# 400_POWER_STAGE.net
KiCad netlist of a schematic drawn in Altium Designer
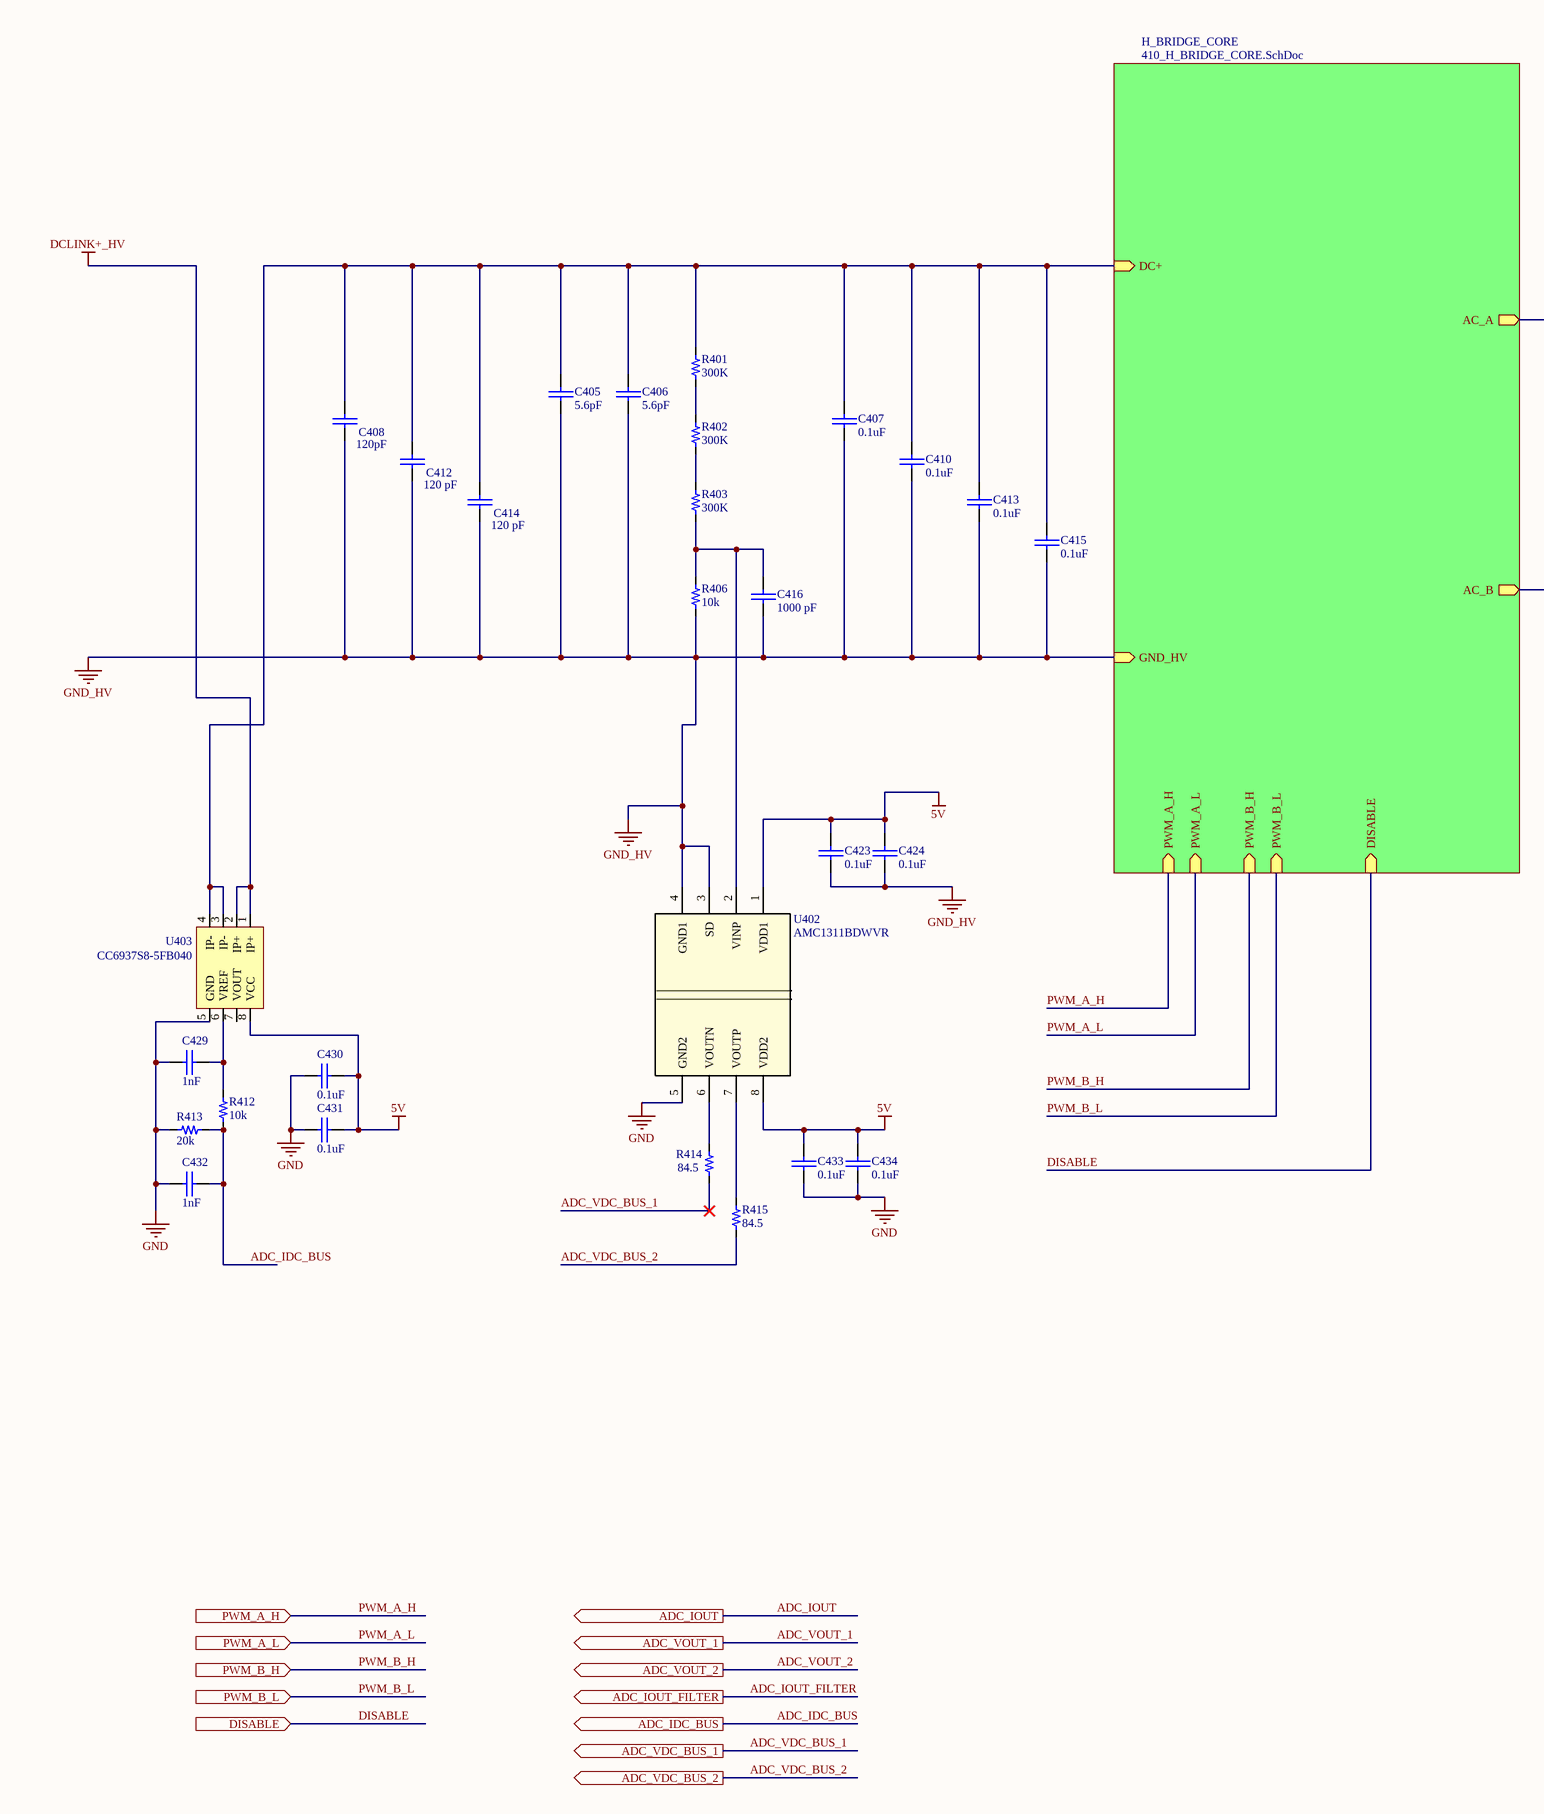
[diagram p0: 400_POWER_STAGE.SchDoc, left]
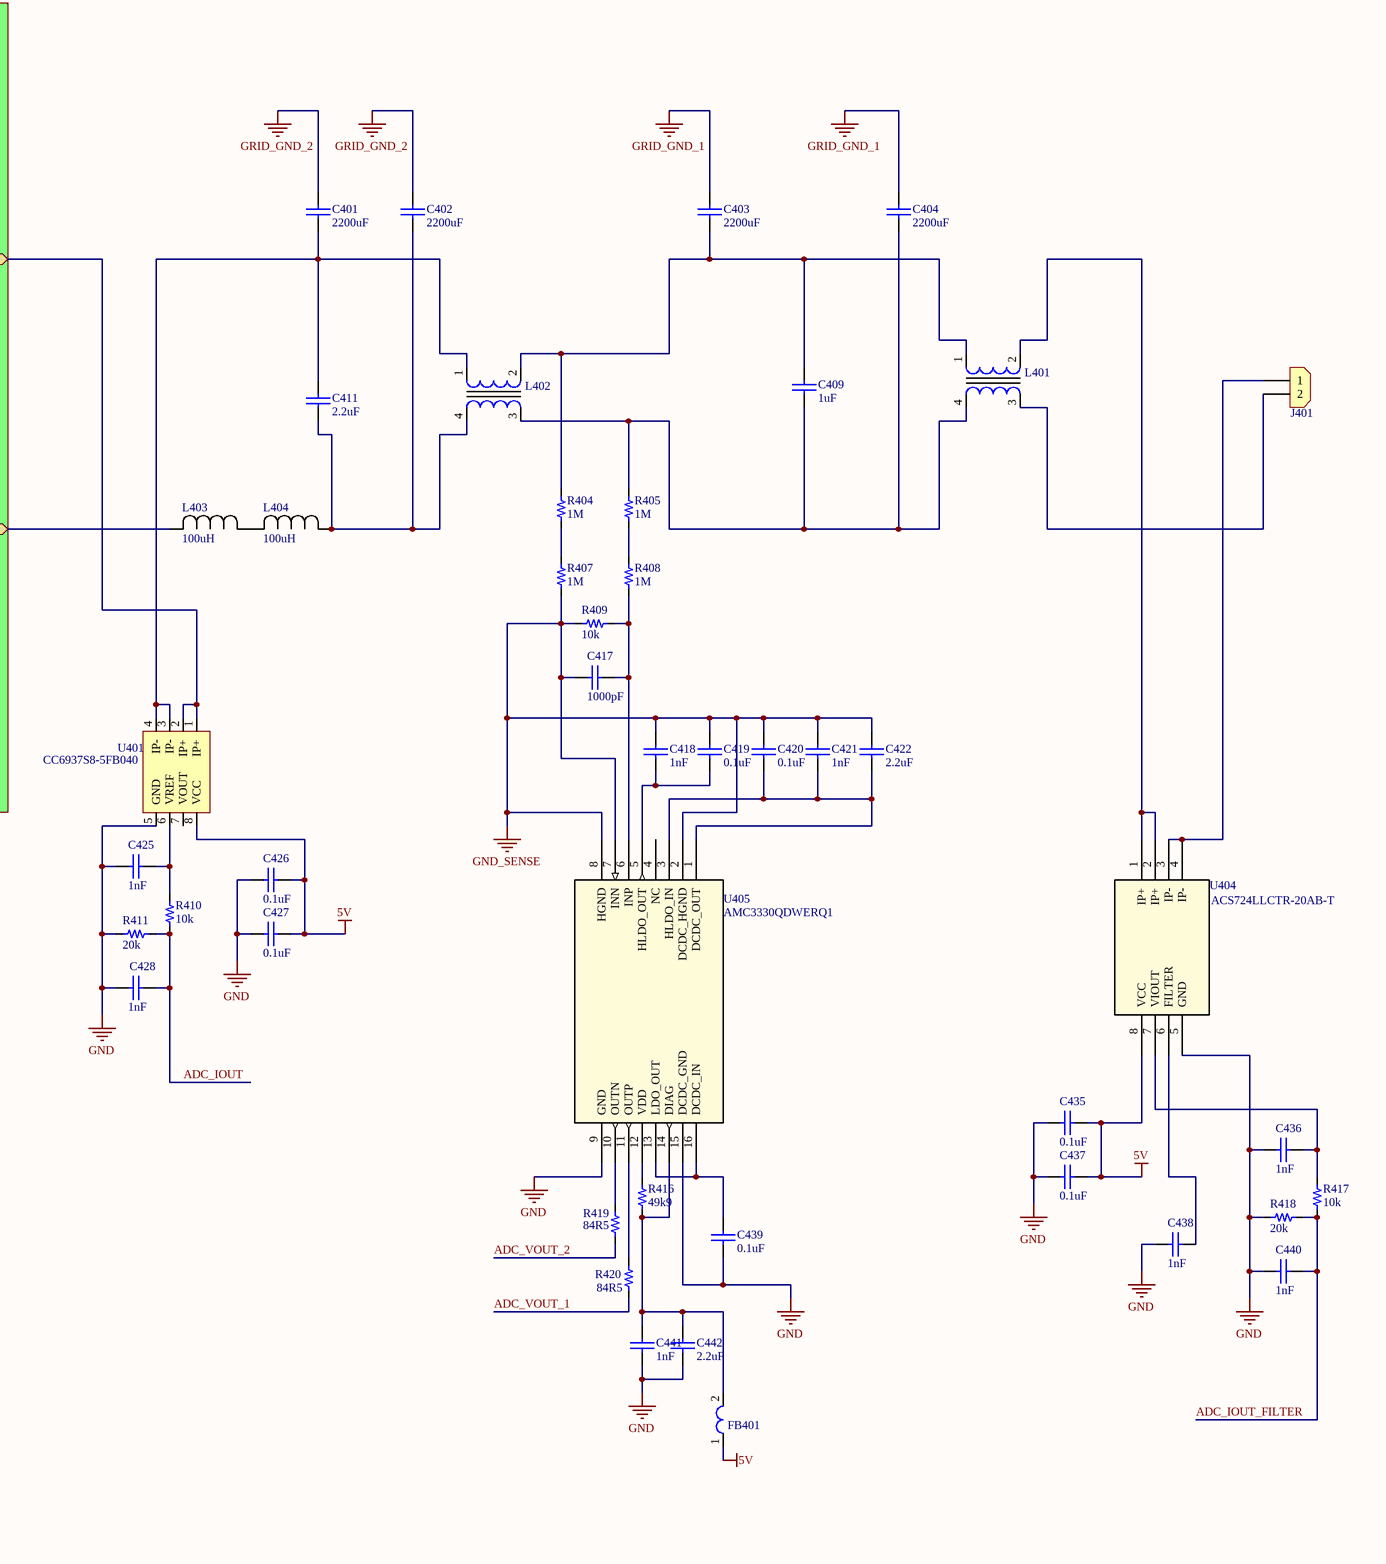
[diagram p1: 400_POWER_STAGE.SchDoc, right]

(export (version "E")
  (design (tool "Eeschema 10.0.6"))
  (components
    (comp (ref "C401")
      (value "2200uF")
      (footprint "Through Hole,P=7.5mm")
      (description "2200 pF ±20% 300VAC Ceramic Capacitor E Radial, Disc")
      (fields
        (field (name "MANUFACTURER") "Murata Electronics")
        (field (name "MANUFACTURER PART NUMBER") "DE6E3KJ222MN3A")
      )
      (libsource (lib "shared_lib_1") (part "CAP_CER_2200PF_300VAC"))
    )
    (comp (ref "C402")
      (value "2200uF")
      (footprint "Through Hole,P=7.5mm")
      (description "2200 pF ±20% 300VAC Ceramic Capacitor E Radial, Disc")
      (fields
        (field (name "MANUFACTURER") "Murata Electronics")
        (field (name "MANUFACTURER PART NUMBER") "DE6E3KJ222MN3A")
      )
      (libsource (lib "shared_lib_1") (part "CAP_CER_2200PF_300VAC"))
    )
    (comp (ref "C403")
      (value "2200uF")
      (footprint "Through Hole,P=7.5mm")
      (description "2200 pF ±20% 300VAC Ceramic Capacitor E Radial, Disc")
      (fields
        (field (name "MANUFACTURER") "Murata Electronics")
        (field (name "MANUFACTURER PART NUMBER") "DE6E3KJ222MN3A")
      )
      (libsource (lib "shared_lib_1") (part "CAP_CER_2200PF_300VAC"))
    )
    (comp (ref "C404")
      (value "2200uF")
      (footprint "Through Hole,P=7.5mm")
      (description "2200 pF ±20% 300VAC Ceramic Capacitor E Radial, Disc")
      (fields
        (field (name "MANUFACTURER") "Murata Electronics")
        (field (name "MANUFACTURER PART NUMBER") "DE6E3KJ222MN3A")
      )
      (libsource (lib "shared_lib_1") (part "CAP_CER_2200PF_300VAC"))
    )
    (comp (ref "C405")
      (value "5.6pF")
      (footprint "0603_cap")
      (description "5.6pF C0G 250V 0603 Ceramic Capacitors RoHS")
      (fields
        (field (name "MANUFACTURER") "Taiyo Yuden")
        (field (name "MANUFACTURER PART NUMBER") "VJ0603D5R6CXPAJ")
      )
      (libsource (lib "shared_lib_1") (part "CAP_CER_5.6pF_C0G_250V_0603"))
    )
    (comp (ref "C406")
      (value "5.6pF")
      (footprint "0603_cap")
      (description "5.6pF C0G 250V 0603 Ceramic Capacitors RoHS")
      (fields
        (field (name "MANUFACTURER") "Taiyo Yuden")
        (field (name "MANUFACTURER PART NUMBER") "VJ0603D5R6CXPAJ")
      )
      (libsource (lib "shared_lib_1") (part "CAP_CER_5.6pF_C0G_250V_0603"))
    )
    (comp (ref "C407")
      (value "0.1uF")
      (footprint "0603_cap")
      (description "CAP CER 100nF 50V Y5V 0603")
      (fields
        (field (name "MANUFACTURER") "FOJAN")
        (field (name "MANUFACTURER PART NUMBER") "FCC0603F104Z500CT")
      )
      (libsource (lib "shared_lib_1") (part "Cap_0.1uF_0603_50V"))
    )
    (comp (ref "C408")
      (value "120pF")
      (footprint "0603_cap")
      (description "120 pF ±5% 250V Capacitores cerámicos C0G, NP0 0603 (1608 métrico)")
      (fields
        (field (name "MANUFACTURER") "YAGEO")
        (field (name "MANUFACTURER PART NUMBER") "CL10B102KB8NNNC")
      )
      (libsource (lib "shared_lib_1") (part "CAP_CER _120PF_250V_0603"))
    )
    (comp (ref "C409")
      (value "1uF")
      (footprint "CAP_2220")
      (description "CAP CER 1uF 450V X7T 2220")
      (fields
        (field (name "MANUFACTURER") "muRata")
        (field (name "MANUFACTURER PART NUMBER") "GC355XD7LP105KX17L")
      )
      (libsource (lib "shared_lib_1") (part "CAP CER 1uF 450V X7T 2220"))
    )
    (comp (ref "C410")
      (value "0.1uF")
      (footprint "0603_cap")
      (description "CAP CER 100nF 50V Y5V 0603")
      (fields
        (field (name "MANUFACTURER") "FOJAN")
        (field (name "MANUFACTURER PART NUMBER") "FCC0603F104Z500CT")
      )
      (libsource (lib "shared_lib_1") (part "Cap_0.1uF_0603_50V"))
    )
    (comp (ref "C411")
      (value "2.2uF")
      (footprint "CAP_2220")
      (description "CAP CER 2.2uF 250V X7R 2220")
      (fields (field (name "MANUFACTURER") "CCTC") (field (name "MANUFACTURER PART NUMBER") "2220B225K251CT"))
      (libsource (lib "shared_lib_1") (part "Cap_2.2uF_2220"))
    )
    (comp (ref "C412")
      (value "120 pF")
      (footprint "0603_cap")
      (description "120 pF ±5% 250V Capacitores cerámicos C0G, NP0 0603 (1608 métrico)")
      (fields
        (field (name "MANUFACTURER") "YAGEO")
        (field (name "MANUFACTURER PART NUMBER") "CL10B102KB8NNNC")
      )
      (libsource (lib "shared_lib_1") (part "CAP_CER _120PF_250V_0603"))
    )
    (comp (ref "C413")
      (value "0.1uF")
      (footprint "0603_cap")
      (description "CAP CER 100nF 50V Y5V 0603")
      (fields
        (field (name "MANUFACTURER") "FOJAN")
        (field (name "MANUFACTURER PART NUMBER") "FCC0603F104Z500CT")
      )
      (libsource (lib "shared_lib_1") (part "Cap_0.1uF_0603_50V"))
    )
    (comp (ref "C414")
      (value "120 pF")
      (footprint "0603_cap")
      (description "120 pF ±5% 250V Capacitores cerámicos C0G, NP0 0603 (1608 métrico)")
      (fields
        (field (name "MANUFACTURER") "YAGEO")
        (field (name "MANUFACTURER PART NUMBER") "CL10B102KB8NNNC")
      )
      (libsource (lib "shared_lib_1") (part "CAP_CER _120PF_250V_0603"))
    )
    (comp (ref "C415")
      (value "0.1uF")
      (footprint "0603_cap")
      (description "CAP CER 100nF 50V Y5V 0603")
      (fields
        (field (name "MANUFACTURER") "FOJAN")
        (field (name "MANUFACTURER PART NUMBER") "FCC0603F104Z500CT")
      )
      (libsource (lib "shared_lib_1") (part "Cap_0.1uF_0603_50V"))
    )
    (comp (ref "C416")
      (value "1000 pF")
      (footprint "0603_cap")
      (description "1000 pF ±10% 10V Ceramic Capacitor X7R 0603 (1608 Metric)")
      (fields
        (field (name "MANUFACTURER") "Johanson Technology Inc.")
        (field (name "MANUFACTURER PART NUMBER") "C0603C102K5RACTU")
      )
      (libsource (lib "shared_lib_1") (part "CAP_CER_1000PF_10V_X7R_0603"))
    )
    (comp (ref "C417")
      (value "1000pF")
      (footprint "0603_cap")
      (description "CAP CER 1nF 100V C0G 0603")
      (fields
        (field (name "MANUFACTURER") "muRata")
        (field (name "MANUFACTURER PART NUMBER") "GRM1885C2A102JA01D")
      )
      (libsource (lib "shared_lib_1") (part "CAP CER 1000pF 100V C0G 0603"))
    )
    (comp (ref "C418")
      (value "1nF")
      (footprint "0603_cap")
      (description "50V 1nF X7R ±10% 0603 Multilayer Ceramic Capacitors MLCC - SMD/SMT ROHS")
      (fields
        (field (name "MANUFACTURER") "YAGEO")
        (field (name "MANUFACTURER PART NUMBER") "CC0603KRX7R9BB102")
      )
      (libsource (lib "shared_lib_1") (part "Cap_1nF_0603_50V"))
    )
    (comp (ref "C419")
      (value "0.1uF")
      (footprint "0603_cap")
      (description "CAP CER 100nF 50V Y5V 0603")
      (fields
        (field (name "MANUFACTURER") "FOJAN")
        (field (name "MANUFACTURER PART NUMBER") "FCC0603F104Z500CT")
      )
      (libsource (lib "shared_lib_1") (part "Cap_0.1uF_0603_50V"))
    )
    (comp (ref "C420")
      (value "0.1uF")
      (footprint "0603_cap")
      (description "CAP CER 100nF 50V Y5V 0603")
      (fields
        (field (name "MANUFACTURER") "FOJAN")
        (field (name "MANUFACTURER PART NUMBER") "FCC0603F104Z500CT")
      )
      (libsource (lib "shared_lib_1") (part "Cap_0.1uF_0603_50V"))
    )
    (comp (ref "C421")
      (value "1nF")
      (footprint "0603_cap")
      (description "50V 1nF X7R ±10% 0603 Multilayer Ceramic Capacitors MLCC - SMD/SMT ROHS")
      (fields
        (field (name "MANUFACTURER") "YAGEO")
        (field (name "MANUFACTURER PART NUMBER") "CC0603KRX7R9BB102")
      )
      (libsource (lib "shared_lib_1") (part "Cap_1nF_0603_50V"))
    )
    (comp (ref "C422")
      (value "2.2uF")
      (footprint "0603_cap")
      (description "CAP CER 2.2uF 16V X7R 0603")
      (fields
        (field (name "MANUFACTURER") "Taiyo Yuden")
        (field (name "MANUFACTURER PART NUMBER") "EMK107BB7225KA-T")
      )
      (libsource (lib "shared_lib_1") (part "CAP CER 2.2uF 16V X7R 0603"))
    )
    (comp (ref "C423")
      (value "0.1uF")
      (footprint "0603_cap")
      (description "CAP CER 100nF 50V Y5V 0603")
      (fields
        (field (name "MANUFACTURER") "FOJAN")
        (field (name "MANUFACTURER PART NUMBER") "FCC0603F104Z500CT")
      )
      (libsource (lib "shared_lib_1") (part "Cap_0.1uF_0603_50V"))
    )
    (comp (ref "C424")
      (value "0.1uF")
      (footprint "0603_cap")
      (description "CAP CER 100nF 50V Y5V 0603")
      (fields
        (field (name "MANUFACTURER") "FOJAN")
        (field (name "MANUFACTURER PART NUMBER") "FCC0603F104Z500CT")
      )
      (libsource (lib "shared_lib_1") (part "Cap_0.1uF_0603_50V"))
    )
    (comp (ref "C425")
      (value "1nF")
      (footprint "0603_cap")
      (description "50V 1nF X7R ±10% 0603 Multilayer Ceramic Capacitors MLCC - SMD/SMT ROHS")
      (fields
        (field (name "MANUFACTURER") "YAGEO")
        (field (name "MANUFACTURER PART NUMBER") "CC0603KRX7R9BB102")
      )
      (libsource (lib "shared_lib_1") (part "Cap_1nF_0603_50V"))
    )
    (comp (ref "C426")
      (value "0.1uF")
      (footprint "0603_cap")
      (description "CAP CER 100nF 50V Y5V 0603")
      (fields
        (field (name "MANUFACTURER") "FOJAN")
        (field (name "MANUFACTURER PART NUMBER") "FCC0603F104Z500CT")
      )
      (libsource (lib "shared_lib_1") (part "Cap_0.1uF_0603_50V"))
    )
    (comp (ref "C427")
      (value "0.1uF")
      (footprint "0603_cap")
      (description "CAP CER 100nF 50V Y5V 0603")
      (fields
        (field (name "MANUFACTURER") "FOJAN")
        (field (name "MANUFACTURER PART NUMBER") "FCC0603F104Z500CT")
      )
      (libsource (lib "shared_lib_1") (part "Cap_0.1uF_0603_50V"))
    )
    (comp (ref "C428")
      (value "1nF")
      (footprint "0603_cap")
      (description "50V 1nF X7R ±10% 0603 Multilayer Ceramic Capacitors MLCC - SMD/SMT ROHS")
      (fields
        (field (name "MANUFACTURER") "YAGEO")
        (field (name "MANUFACTURER PART NUMBER") "CC0603KRX7R9BB102")
      )
      (libsource (lib "shared_lib_1") (part "Cap_1nF_0603_50V"))
    )
    (comp (ref "C429")
      (value "1nF")
      (footprint "0603_cap")
      (description "50V 1nF X7R ±10% 0603 Multilayer Ceramic Capacitors MLCC - SMD/SMT ROHS")
      (fields
        (field (name "MANUFACTURER") "YAGEO")
        (field (name "MANUFACTURER PART NUMBER") "CC0603KRX7R9BB102")
      )
      (libsource (lib "shared_lib_1") (part "Cap_1nF_0603_50V"))
    )
    (comp (ref "C430")
      (value "0.1uF")
      (footprint "0603_cap")
      (description "CAP CER 100nF 50V Y5V 0603")
      (fields
        (field (name "MANUFACTURER") "FOJAN")
        (field (name "MANUFACTURER PART NUMBER") "FCC0603F104Z500CT")
      )
      (libsource (lib "shared_lib_1") (part "Cap_0.1uF_0603_50V"))
    )
    (comp (ref "C431")
      (value "0.1uF")
      (footprint "0603_cap")
      (description "CAP CER 100nF 50V Y5V 0603")
      (fields
        (field (name "MANUFACTURER") "FOJAN")
        (field (name "MANUFACTURER PART NUMBER") "FCC0603F104Z500CT")
      )
      (libsource (lib "shared_lib_1") (part "Cap_0.1uF_0603_50V"))
    )
    (comp (ref "C432")
      (value "1nF")
      (footprint "0603_cap")
      (description "50V 1nF X7R ±10% 0603 Multilayer Ceramic Capacitors MLCC - SMD/SMT ROHS")
      (fields
        (field (name "MANUFACTURER") "YAGEO")
        (field (name "MANUFACTURER PART NUMBER") "CC0603KRX7R9BB102")
      )
      (libsource (lib "shared_lib_1") (part "Cap_1nF_0603_50V"))
    )
    (comp (ref "C433")
      (value "0.1uF")
      (footprint "0603_cap")
      (description "CAP CER 100nF 50V Y5V 0603")
      (fields
        (field (name "MANUFACTURER") "FOJAN")
        (field (name "MANUFACTURER PART NUMBER") "FCC0603F104Z500CT")
      )
      (libsource (lib "shared_lib_1") (part "Cap_0.1uF_0603_50V"))
    )
    (comp (ref "C434")
      (value "0.1uF")
      (footprint "0603_cap")
      (description "CAP CER 100nF 50V Y5V 0603")
      (fields
        (field (name "MANUFACTURER") "FOJAN")
        (field (name "MANUFACTURER PART NUMBER") "FCC0603F104Z500CT")
      )
      (libsource (lib "shared_lib_1") (part "Cap_0.1uF_0603_50V"))
    )
    (comp (ref "C435")
      (value "0.1uF")
      (footprint "0603_cap")
      (description "CAP CER 100nF 50V Y5V 0603")
      (fields
        (field (name "MANUFACTURER") "FOJAN")
        (field (name "MANUFACTURER PART NUMBER") "FCC0603F104Z500CT")
      )
      (libsource (lib "shared_lib_1") (part "Cap_0.1uF_0603_50V"))
    )
    (comp (ref "C436")
      (value "1nF")
      (footprint "0603_cap")
      (description "50V 1nF X7R ±10% 0603 Multilayer Ceramic Capacitors MLCC - SMD/SMT ROHS")
      (fields
        (field (name "MANUFACTURER") "YAGEO")
        (field (name "MANUFACTURER PART NUMBER") "CC0603KRX7R9BB102")
      )
      (libsource (lib "shared_lib_1") (part "Cap_1nF_0603_50V"))
    )
    (comp (ref "C437")
      (value "0.1uF")
      (footprint "0603_cap")
      (description "CAP CER 100nF 50V Y5V 0603")
      (fields
        (field (name "MANUFACTURER") "FOJAN")
        (field (name "MANUFACTURER PART NUMBER") "FCC0603F104Z500CT")
      )
      (libsource (lib "shared_lib_1") (part "Cap_0.1uF_0603_50V"))
    )
    (comp (ref "C438")
      (value "1nF")
      (footprint "0603_cap")
      (description "50V 1nF X7R ±10% 0603 Multilayer Ceramic Capacitors MLCC - SMD/SMT ROHS")
      (fields
        (field (name "MANUFACTURER") "YAGEO")
        (field (name "MANUFACTURER PART NUMBER") "CC0603KRX7R9BB102")
      )
      (libsource (lib "shared_lib_1") (part "Cap_1nF_0603_50V"))
    )
    (comp (ref "C439")
      (value "0.1uF")
      (footprint "0603_cap")
      (description "CAP CER 100nF 50V Y5V 0603")
      (fields
        (field (name "MANUFACTURER") "FOJAN")
        (field (name "MANUFACTURER PART NUMBER") "FCC0603F104Z500CT")
      )
      (libsource (lib "shared_lib_1") (part "Cap_0.1uF_0603_50V"))
    )
    (comp (ref "C440")
      (value "1nF")
      (footprint "0603_cap")
      (description "50V 1nF X7R ±10% 0603 Multilayer Ceramic Capacitors MLCC - SMD/SMT ROHS")
      (fields
        (field (name "MANUFACTURER") "YAGEO")
        (field (name "MANUFACTURER PART NUMBER") "CC0603KRX7R9BB102")
      )
      (libsource (lib "shared_lib_1") (part "Cap_1nF_0603_50V"))
    )
    (comp (ref "C441")
      (value "1nF")
      (footprint "0603_cap")
      (description "50V 1nF X7R ±10% 0603 Multilayer Ceramic Capacitors MLCC - SMD/SMT ROHS")
      (fields
        (field (name "MANUFACTURER") "YAGEO")
        (field (name "MANUFACTURER PART NUMBER") "CC0603KRX7R9BB102")
      )
      (libsource (lib "shared_lib_1") (part "Cap_1nF_0603_50V"))
    )
    (comp (ref "C442")
      (value "2.2uF")
      (footprint "0603_cap")
      (description "CAP CER 2.2uF 16V X7R 0603")
      (fields
        (field (name "MANUFACTURER") "Taiyo Yuden")
        (field (name "MANUFACTURER PART NUMBER") "EMK107BB7225KA-T")
      )
      (libsource (lib "shared_lib_1") (part "CAP CER 2.2uF 16V X7R 0603"))
    )
    (comp (ref "FB401")
      (value "~")
      (footprint "MH1608")
      (description "FERRITE BEAD 600 OHM 0603 4LN")
      (fields
        (field (name "MANUFACTURER") "Bourns Inc.")
        (field (name "MANUFACTURER PART NUMBER") "MH1608-601Y")
      )
      (libsource (lib "shared_lib_1") (part "FERRITE_BEAD_600_OHM"))
    )
    (comp (ref "J401")
      (value "~")
      (footprint "CON_2x1_TH_5MM")
      (description "2POS 5MM")
      (fields (field (name "MANUFACTURER") "JILN") (field (name "MANUFACTURER PART NUMBER") "JL126-50002G01"))
      (libsource (lib "shared_lib_1") (part "Con_2x1_TH_5mm"))
    )
    (comp (ref "L401")
      (value "~")
      (footprint "PH9455405NL")
      (description "4.5 mH @ 4 MHz 2 Line Common Mode Choke Through Hole 4.4 kOhms @ 4 MHz 12A DCR 8.5mOhm")
      (fields
        (field (name "MANUFACTURER") "WurthPULSE Elektronik")
        (field (name "MANUFACTURER PART NUMBER") "PH9455.405NL")
      )
      (libsource (lib "shared_lib_1") (part "CMC 4.5MH 12A 2LN 4.4 KOHM TH"))
    )
    (comp (ref "L402")
      (value "~")
      (footprint "PH9455405NL")
      (description "4.5 mH @ 4 MHz 2 Line Common Mode Choke Through Hole 4.4 kOhms @ 4 MHz 12A DCR 8.5mOhm")
      (fields
        (field (name "MANUFACTURER") "WurthPULSE Elektronik")
        (field (name "MANUFACTURER PART NUMBER") "PH9455.405NL")
      )
      (libsource (lib "shared_lib_1") (part "CMC 4.5MH 12A 2LN 4.4 KOHM TH"))
    )
    (comp (ref "L403")
      (value "100uH")
      (footprint "IND-SMD_L13.7-W12.8_FCH1365")
      (description "200 µH Unshielded Drum Core, Wirewound Inductor 3 A 80mOhm Max Radial, Horizontal Cylinder (Open)")
      (fields
        (field (name "MANUFACTURER") "FANGCHENG")
        (field (name "MANUFACTURER PART NUMBER") "FCH1365-101M")
      )
      (libsource (lib "shared_lib_1") (part "FIXED_IND_100UH_3A_1"))
    )
    (comp (ref "L404")
      (value "100uH")
      (footprint "IND-SMD_L13.7-W12.8_FCH1365")
      (description "200 µH Unshielded Drum Core, Wirewound Inductor 3 A 80mOhm Max Radial, Horizontal Cylinder (Open)")
      (fields
        (field (name "MANUFACTURER") "FANGCHENG")
        (field (name "MANUFACTURER PART NUMBER") "FCH1365-101M")
      )
      (libsource (lib "shared_lib_1") (part "FIXED_IND_100UH_3A_1"))
    )
    (comp (ref "R401")
      (value "300K")
      (footprint "0603_res")
      (description "300 kOhms ±1% 0.1W, 1/10W Chip Resistor 0603 (1608 Metric) Moisture Resistant Thick Film")
      (fields
        (field (name "MANUFACTURER") "YAGEO")
        (field (name "MANUFACTURER PART NUMBER") "RC0603FR-07300KL")
      )
      (libsource (lib "shared_lib_1") (part "RES_300K_OHM_0603"))
    )
    (comp (ref "R402")
      (value "300K")
      (footprint "0603_res")
      (description "300 kOhms ±1% 0.1W, 1/10W Chip Resistor 0603 (1608 Metric) Moisture Resistant Thick Film")
      (fields
        (field (name "MANUFACTURER") "YAGEO")
        (field (name "MANUFACTURER PART NUMBER") "RC0603FR-07300KL")
      )
      (libsource (lib "shared_lib_1") (part "RES_300K_OHM_0603"))
    )
    (comp (ref "R403")
      (value "300K")
      (footprint "0603_res")
      (description "300 kOhms ±1% 0.1W, 1/10W Chip Resistor 0603 (1608 Metric) Moisture Resistant Thick Film")
      (fields
        (field (name "MANUFACTURER") "YAGEO")
        (field (name "MANUFACTURER PART NUMBER") "RC0603FR-07300KL")
      )
      (libsource (lib "shared_lib_1") (part "RES_300K_OHM_0603"))
    )
    (comp (ref "R404")
      (value "1M")
      (footprint "0603_res")
      (description "1 MOhms ±1% 0.125W, 1/8W Chip Resistor 0603 (1608 Metric) Automotive AEC-Q200 Thick Film")
      (fields
        (field (name "MANUFACTURER") "Vishay Dale")
        (field (name "MANUFACTURER PART NUMBER") "CRCW06031M00FKEA")
      )
      (libsource (lib "shared_lib_1") (part "RES_SMD_1M_OHM_0603"))
    )
    (comp (ref "R405")
      (value "1M")
      (footprint "0603_res")
      (description "1 MOhms ±1% 0.125W, 1/8W Chip Resistor 0603 (1608 Metric) Automotive AEC-Q200 Thick Film")
      (fields
        (field (name "MANUFACTURER") "Vishay Dale")
        (field (name "MANUFACTURER PART NUMBER") "CRCW06031M00FKEA")
      )
      (libsource (lib "shared_lib_1") (part "RES_SMD_1M_OHM_0603"))
    )
    (comp (ref "R406")
      (value "10k")
      (footprint "0603_res")
      (description "RES SMD 10k OHM 5% 1/10W 0603")
      (fields (field (name "MANUFACTURER") "FOJAN") (field (name "MANUFACTURER PART NUMBER") "FRC0603J103TS"))
      (libsource (lib "shared_lib_1") (part "Res_10k_0603_1/10W"))
    )
    (comp (ref "R407")
      (value "1M")
      (footprint "0603_res")
      (description "1 MOhms ±1% 0.125W, 1/8W Chip Resistor 0603 (1608 Metric) Automotive AEC-Q200 Thick Film")
      (fields
        (field (name "MANUFACTURER") "Vishay Dale")
        (field (name "MANUFACTURER PART NUMBER") "CRCW06031M00FKEA")
      )
      (libsource (lib "shared_lib_1") (part "RES_SMD_1M_OHM_0603"))
    )
    (comp (ref "R408")
      (value "1M")
      (footprint "0603_res")
      (description "1 MOhms ±1% 0.125W, 1/8W Chip Resistor 0603 (1608 Metric) Automotive AEC-Q200 Thick Film")
      (fields
        (field (name "MANUFACTURER") "Vishay Dale")
        (field (name "MANUFACTURER PART NUMBER") "CRCW06031M00FKEA")
      )
      (libsource (lib "shared_lib_1") (part "RES_SMD_1M_OHM_0603"))
    )
    (comp (ref "R409")
      (value "10k")
      (footprint "0603_res")
      (description "RES SMD 10k OHM 5% 1/10W 0603")
      (fields (field (name "MANUFACTURER") "FOJAN") (field (name "MANUFACTURER PART NUMBER") "FRC0603J103TS"))
      (libsource (lib "shared_lib_1") (part "Res_10k_0603_1/10W"))
    )
    (comp (ref "R410")
      (value "10k")
      (footprint "0603_res")
      (description "RES SMD 10k OHM 5% 1/10W 0603")
      (fields (field (name "MANUFACTURER") "FOJAN") (field (name "MANUFACTURER PART NUMBER") "FRC0603J103TS"))
      (libsource (lib "shared_lib_1") (part "Res_10k_0603_1/10W"))
    )
    (comp (ref "R411")
      (value "20k")
      (footprint "0603_res")
      (description "RES 20kΩ ±1% 100mW 0603")
      (fields
        (field (name "MANUFACTURER") "FOJAN")
        (field (name "MANUFACTURER PART NUMBER") "FRC0603F2002TS")
      )
      (libsource (lib "shared_lib_1") (part "RES_20K_OHM_0603"))
    )
    (comp (ref "R412")
      (value "10k")
      (footprint "0603_res")
      (description "RES SMD 10k OHM 5% 1/10W 0603")
      (fields (field (name "MANUFACTURER") "FOJAN") (field (name "MANUFACTURER PART NUMBER") "FRC0603J103TS"))
      (libsource (lib "shared_lib_1") (part "Res_10k_0603_1/10W"))
    )
    (comp (ref "R413")
      (value "20k")
      (footprint "0603_res")
      (description "RES 20kΩ ±1% 100mW 0603")
      (fields
        (field (name "MANUFACTURER") "FOJAN")
        (field (name "MANUFACTURER PART NUMBER") "FRC0603F2002TS")
      )
      (libsource (lib "shared_lib_1") (part "RES_20K_OHM_0603"))
    )
    (comp (ref "R414")
      (value "84.5")
      (footprint "0603_res")
      (description "100mW Thick Film Resistor 50V ±100ppm/℃ ±1% 84.5Ω 0603 Chip Resistor - Surface Mount ROHS")
      (fields
        (field (name "MANUFACTURER") "LIZ Elec")
        (field (name "MANUFACTURER PART NUMBER") "CR0603FA84R5G")
      )
      (libsource (lib "shared_lib_1") (part "Res_84R5_0603_1/10W"))
    )
    (comp (ref "R415")
      (value "84.5")
      (footprint "0603_res")
      (description "100mW Thick Film Resistor 50V ±100ppm/℃ ±1% 84.5Ω 0603 Chip Resistor - Surface Mount ROHS")
      (fields
        (field (name "MANUFACTURER") "LIZ Elec")
        (field (name "MANUFACTURER PART NUMBER") "CR0603FA84R5G")
      )
      (libsource (lib "shared_lib_1") (part "Res_84R5_0603_1/10W"))
    )
    (comp (ref "R416")
      (value "49k9")
      (footprint "0603_res")
      (description "100mW Thick Film Resistor 75V ±100ppm/℃ ±1% 49.9kΩ 0603 Chip Resistor - Surface Mount ROHS")
      (fields
        (field (name "MANUFACTURER") "YAGEO")
        (field (name "MANUFACTURER PART NUMBER") "RC0603FR-0749K9L")
      )
      (libsource (lib "shared_lib_1") (part "Res_49k9_0603_1/10W"))
    )
    (comp (ref "R417")
      (value "10k")
      (footprint "0603_res")
      (description "RES SMD 10k OHM 5% 1/10W 0603")
      (fields (field (name "MANUFACTURER") "FOJAN") (field (name "MANUFACTURER PART NUMBER") "FRC0603J103TS"))
      (libsource (lib "shared_lib_1") (part "Res_10k_0603_1/10W"))
    )
    (comp (ref "R418")
      (value "20k")
      (footprint "0603_res")
      (description "RES 20kΩ ±1% 100mW 0603")
      (fields
        (field (name "MANUFACTURER") "FOJAN")
        (field (name "MANUFACTURER PART NUMBER") "FRC0603F2002TS")
      )
      (libsource (lib "shared_lib_1") (part "RES_20K_OHM_0603"))
    )
    (comp (ref "R419")
      (value "84R5")
      (footprint "0603_res")
      (description "100mW Thick Film Resistor 50V ±100ppm/℃ ±1% 84.5Ω 0603 Chip Resistor - Surface Mount ROHS")
      (fields
        (field (name "MANUFACTURER") "LIZ Elec")
        (field (name "MANUFACTURER PART NUMBER") "CR0603FA84R5G")
      )
      (libsource (lib "shared_lib_1") (part "Res_84R5_0603_1/10W"))
    )
    (comp (ref "R420")
      (value "84R5")
      (footprint "0603_res")
      (description "100mW Thick Film Resistor 50V ±100ppm/℃ ±1% 84.5Ω 0603 Chip Resistor - Surface Mount ROHS")
      (fields
        (field (name "MANUFACTURER") "LIZ Elec")
        (field (name "MANUFACTURER PART NUMBER") "CR0603FA84R5G")
      )
      (libsource (lib "shared_lib_1") (part "Res_84R5_0603_1/10W"))
    )
    (comp (ref "U401")
      (value "~")
      (footprint "SOP-8_L4.9")
      (description "High-performance Hall effect current sensor")
      (fields
        (field (name "MANUFACTURER") "Cross chip")
        (field (name "MANUFACTURER PART NUMBER") "CC6937S8-5FB040")
      )
      (libsource (lib "shared_lib_1") (part "Cross chip CC6937S8-5FB040"))
    )
    (comp (ref "U402")
      (value "AMC1311BDWVR")
      (footprint "DWV0008A")
      (description "Aislamiento CI 8-SOIC")
      (fields (field (name "MANUFACTURER") "Texas Instruments"))
      (libsource (lib "shared_lib_1") (part "IC ISOLATION 8SOIC"))
    )
    (comp (ref "U403")
      (value "~")
      (footprint "SOP-8_L4.9")
      (description "High-performance Hall effect current sensor")
      (fields
        (field (name "MANUFACTURER") "Cross chip")
        (field (name "MANUFACTURER PART NUMBER") "CC6937S8-5FB040")
      )
      (libsource (lib "shared_lib_1") (part "Cross chip CC6937S8-5FB040"))
    )
    (comp (ref "U404")
      (value "~")
      (footprint "SOICN8_LC_ALM")
      (fields
        (field (name "MANUFACTURER PART NUMBER") "ACS724LLCTR-20AB-T")
        (field (name "MANUFACTURER") "Allegro MicroSystems")
      )
      (libsource (lib "shared_lib_1") (part "CURRENT SENSOR 20A"))
    )
    (comp (ref "U405")
      (value "AMC3330QDWERQ1")
      (footprint "SOIC16_DWE_TEX")
      (description "Precision, ±1V input, enhanced isolation amplifier with integrated DC/DC converter")
      (fields (field (name "MANUFACTURER") "Texas Instruments"))
      (libsource (lib "shared_lib_1") (part "IC ISOLATED AMPLIFIER"))
    )
  )
  (nets
    (net (code "1") (name "/AC_A") (class "Default")
      (node (ref "U401") (pin "1") (pinfunction "IP+_1") (pintype "power_in"))
      (node (ref "U401") (pin "2") (pinfunction "IP+_2") (pintype "power_in"))
    )
    (net (code "2") (name "/AC_B") (class "Default")
      (node (ref "L403") (pin "2") (pinfunction "2_2") (pintype "passive"))
    )
    (net (code "3") (name "/ADC_IDC_BUS") (class "Default")
      (node (ref "C432") (pin "2") (pinfunction "2_2") (pintype "passive"))
      (node (ref "R412") (pin "1") (pinfunction "1_1") (pintype "passive"))
      (node (ref "R413") (pin "2") (pinfunction "2_2") (pintype "passive"))
    )
    (net (code "4") (name "/ADC_IOUT") (class "Default")
      (node (ref "C428") (pin "2") (pinfunction "2_2") (pintype "passive"))
      (node (ref "R410") (pin "1") (pinfunction "1_1") (pintype "passive"))
      (node (ref "R411") (pin "2") (pinfunction "2_2") (pintype "passive"))
    )
    (net (code "5") (name "/ADC_IOUT_FILTER") (class "Default")
      (node (ref "C440") (pin "2") (pinfunction "2_2") (pintype "passive"))
      (node (ref "R417") (pin "1") (pinfunction "1_1") (pintype "passive"))
      (node (ref "R418") (pin "2") (pinfunction "2_2") (pintype "passive"))
    )
    (net (code "6") (name "/ADC_VDC_BUS_1") (class "Default")
      (node (ref "R414") (pin "1") (pinfunction "1_1") (pintype "passive+no_connect"))
    )
    (net (code "7") (name "/ADC_VDC_BUS_2") (class "Default")
      (node (ref "R415") (pin "1") (pinfunction "1_1") (pintype "passive"))
    )
    (net (code "8") (name "/ADC_VOUT_1") (class "Default")
      (node (ref "R420") (pin "1") (pinfunction "1_1") (pintype "passive"))
    )
    (net (code "9") (name "/ADC_VOUT_2") (class "Default")
      (node (ref "R419") (pin "1") (pinfunction "1_1") (pintype "passive"))
    )
    (net (code "10") (name "/DC+") (class "Default")
      (node (ref "C405") (pin "1") (pinfunction "1_1") (pintype "passive"))
      (node (ref "C406") (pin "1") (pinfunction "1_1") (pintype "passive"))
      (node (ref "C407") (pin "1") (pinfunction "1_1") (pintype "passive"))
      (node (ref "C408") (pin "1") (pinfunction "1_1") (pintype "passive"))
      (node (ref "C410") (pin "1") (pinfunction "1_1") (pintype "passive"))
      (node (ref "C412") (pin "1") (pinfunction "1_1") (pintype "passive"))
      (node (ref "C413") (pin "1") (pinfunction "1_1") (pintype "passive"))
      (node (ref "C414") (pin "1") (pinfunction "1_1") (pintype "passive"))
      (node (ref "C415") (pin "1") (pinfunction "1_1") (pintype "passive"))
      (node (ref "R401") (pin "2") (pinfunction "2_2") (pintype "passive"))
      (node (ref "U403") (pin "3") (pinfunction "IP-_3") (pintype "power_in"))
      (node (ref "U403") (pin "4") (pinfunction "IP-_4") (pintype "power_in"))
    )
    (net (code "16") (name "5V") (class "Default")
      (node (ref "C423") (pin "1") (pinfunction "1_1") (pintype "passive"))
      (node (ref "C424") (pin "1") (pinfunction "1_1") (pintype "passive"))
      (node (ref "C426") (pin "2") (pinfunction "2_2") (pintype "passive"))
      (node (ref "C427") (pin "2") (pinfunction "2_2") (pintype "passive"))
      (node (ref "C430") (pin "2") (pinfunction "2_2") (pintype "passive"))
      (node (ref "C431") (pin "2") (pinfunction "2_2") (pintype "passive"))
      (node (ref "C433") (pin "1") (pinfunction "1_1") (pintype "passive"))
      (node (ref "C434") (pin "1") (pinfunction "1_1") (pintype "passive"))
      (node (ref "C435") (pin "2") (pinfunction "2_2") (pintype "passive"))
      (node (ref "C437") (pin "2") (pinfunction "2_2") (pintype "passive"))
      (node (ref "FB401") (pin "1") (pinfunction "1_1") (pintype "passive"))
      (node (ref "U401") (pin "8") (pinfunction "VCC_8") (pintype "passive"))
      (node (ref "U402") (pin "1") (pinfunction "VDD1_1") (pintype "power_in"))
      (node (ref "U402") (pin "8") (pinfunction "VDD2_8") (pintype "power_in"))
      (node (ref "U403") (pin "8") (pinfunction "VCC_8") (pintype "passive"))
      (node (ref "U404") (pin "8") (pinfunction "VCC_8") (pintype "power_in"))
    )
    (net (code "17") (name "DCLINK+_HV") (class "Default")
      (node (ref "U403") (pin "1") (pinfunction "IP+_1") (pintype "power_in"))
      (node (ref "U403") (pin "2") (pinfunction "IP+_2") (pintype "power_in"))
    )
    (net (code "18") (name "GND") (class "Default")
      (node (ref "C425") (pin "2") (pinfunction "2_2") (pintype "passive"))
      (node (ref "C426") (pin "1") (pinfunction "1_1") (pintype "passive"))
      (node (ref "C427") (pin "1") (pinfunction "1_1") (pintype "passive"))
      (node (ref "C428") (pin "1") (pinfunction "1_1") (pintype "passive"))
      (node (ref "C429") (pin "2") (pinfunction "2_2") (pintype "passive"))
      (node (ref "C430") (pin "1") (pinfunction "1_1") (pintype "passive"))
      (node (ref "C431") (pin "1") (pinfunction "1_1") (pintype "passive"))
      (node (ref "C432") (pin "1") (pinfunction "1_1") (pintype "passive"))
      (node (ref "C433") (pin "2") (pinfunction "2_2") (pintype "passive"))
      (node (ref "C434") (pin "2") (pinfunction "2_2") (pintype "passive"))
      (node (ref "C435") (pin "1") (pinfunction "1_1") (pintype "passive"))
      (node (ref "C436") (pin "2") (pinfunction "2_2") (pintype "passive"))
      (node (ref "C437") (pin "1") (pinfunction "1_1") (pintype "passive"))
      (node (ref "C438") (pin "2") (pinfunction "2_2") (pintype "passive"))
      (node (ref "C439") (pin "2") (pinfunction "2_2") (pintype "passive"))
      (node (ref "C440") (pin "1") (pinfunction "1_1") (pintype "passive"))
      (node (ref "C441") (pin "2") (pinfunction "2_2") (pintype "passive"))
      (node (ref "C442") (pin "2") (pinfunction "2_2") (pintype "passive"))
      (node (ref "R411") (pin "1") (pinfunction "1_1") (pintype "passive"))
      (node (ref "R413") (pin "1") (pinfunction "1_1") (pintype "passive"))
      (node (ref "R418") (pin "1") (pinfunction "1_1") (pintype "passive"))
      (node (ref "U401") (pin "5") (pinfunction "GND_5") (pintype "passive"))
      (node (ref "U402") (pin "5") (pinfunction "GND2_5") (pintype "power_in"))
      (node (ref "U403") (pin "5") (pinfunction "GND_5") (pintype "passive"))
      (node (ref "U404") (pin "5") (pinfunction "GND_5") (pintype "power_in"))
      (node (ref "U405") (pin "15") (pinfunction "DCDC_GND_15") (pintype "power_in"))
      (node (ref "U405") (pin "9") (pinfunction "GND_9") (pintype "power_in"))
    )
    (net (code "19") (name "GND_HV") (class "Default")
      (node (ref "C405") (pin "2") (pinfunction "2_2") (pintype "passive"))
      (node (ref "C406") (pin "2") (pinfunction "2_2") (pintype "passive"))
      (node (ref "C407") (pin "2") (pinfunction "2_2") (pintype "passive"))
      (node (ref "C408") (pin "2") (pinfunction "2_2") (pintype "passive"))
      (node (ref "C410") (pin "2") (pinfunction "2_2") (pintype "passive"))
      (node (ref "C412") (pin "2") (pinfunction "2_2") (pintype "passive"))
      (node (ref "C413") (pin "2") (pinfunction "2_2") (pintype "passive"))
      (node (ref "C414") (pin "2") (pinfunction "2_2") (pintype "passive"))
      (node (ref "C415") (pin "2") (pinfunction "2_2") (pintype "passive"))
      (node (ref "C416") (pin "2") (pinfunction "2_2") (pintype "passive"))
      (node (ref "C423") (pin "2") (pinfunction "2_2") (pintype "passive"))
      (node (ref "C424") (pin "2") (pinfunction "2_2") (pintype "passive"))
      (node (ref "R406") (pin "1") (pinfunction "1_1") (pintype "passive"))
      (node (ref "U402") (pin "3") (pinfunction "SD_3") (pintype "passive"))
      (node (ref "U402") (pin "4") (pinfunction "GND1_4") (pintype "passive"))
    )
    (net (code "20") (name "GND_SENSE") (class "Default")
      (node (ref "C417") (pin "1") (pinfunction "1_1") (pintype "passive"))
      (node (ref "C418") (pin "1") (pinfunction "1_1") (pintype "passive"))
      (node (ref "C419") (pin "1") (pinfunction "1_1") (pintype "passive"))
      (node (ref "C420") (pin "1") (pinfunction "1_1") (pintype "passive"))
      (node (ref "C421") (pin "1") (pinfunction "1_1") (pintype "passive"))
      (node (ref "C422") (pin "1") (pinfunction "1_1") (pintype "passive"))
      (node (ref "R407") (pin "1") (pinfunction "1_1") (pintype "passive"))
      (node (ref "R409") (pin "1") (pinfunction "1_1") (pintype "passive"))
      (node (ref "U405") (pin "2") (pinfunction "DCDC_HGND_2") (pintype "power_in"))
      (node (ref "U405") (pin "7") (pinfunction "INN_7") (pintype "input"))
      (node (ref "U405") (pin "8") (pinfunction "HGND_8") (pintype "power_in"))
    )
    (net (code "21") (name "GRID_GND_1") (class "Default")
      (node (ref "C403") (pin "1") (pinfunction "1_1") (pintype "passive"))
      (node (ref "C404") (pin "1") (pinfunction "1_1") (pintype "passive"))
    )
    (net (code "22") (name "GRID_GND_2") (class "Default")
      (node (ref "C401") (pin "1") (pinfunction "1_1") (pintype "passive"))
      (node (ref "C402") (pin "1") (pinfunction "1_1") (pintype "passive"))
    )
    (net (code "23") (name "Net-(C401-Pad2)") (class "Default")
      (node (ref "C401") (pin "2") (pinfunction "2_2") (pintype "passive"))
      (node (ref "C411") (pin "2") (pinfunction "2_2") (pintype "passive"))
      (node (ref "L402") (pin "1") (pinfunction "1_1") (pintype "passive"))
      (node (ref "U401") (pin "3") (pinfunction "IP-_3") (pintype "power_in"))
      (node (ref "U401") (pin "4") (pinfunction "IP-_4") (pintype "power_in"))
    )
    (net (code "24") (name "Net-(C402-Pad2)") (class "Default")
      (node (ref "C402") (pin "2") (pinfunction "2_2") (pintype "passive"))
      (node (ref "C411") (pin "1") (pinfunction "1_1") (pintype "passive"))
      (node (ref "L402") (pin "4") (pinfunction "4_4") (pintype "passive"))
      (node (ref "L404") (pin "1") (pinfunction "1_1") (pintype "passive"))
    )
    (net (code "25") (name "Net-(C403-Pad2)") (class "Default")
      (node (ref "C403") (pin "2") (pinfunction "2_2") (pintype "passive"))
      (node (ref "C409") (pin "1") (pinfunction "1_1") (pintype "passive"))
      (node (ref "L401") (pin "1") (pinfunction "1_1") (pintype "passive"))
      (node (ref "L402") (pin "2") (pinfunction "2_2") (pintype "passive"))
      (node (ref "R404") (pin "2") (pinfunction "2_2") (pintype "passive"))
    )
    (net (code "26") (name "Net-(C404-Pad2)") (class "Default")
      (node (ref "C404") (pin "2") (pinfunction "2_2") (pintype "passive"))
      (node (ref "C409") (pin "2") (pinfunction "2_2") (pintype "passive"))
      (node (ref "L401") (pin "4") (pinfunction "4_4") (pintype "passive"))
      (node (ref "L402") (pin "3") (pinfunction "3_3") (pintype "passive"))
      (node (ref "R405") (pin "2") (pinfunction "2_2") (pintype "passive"))
    )
    (net (code "27") (name "Net-(J401-Pad1)") (class "Default")
      (node (ref "J401") (pin "1") (pinfunction "1_1") (pintype "passive"))
      (node (ref "U404") (pin "3") (pinfunction "IP-_3") (pintype "passive"))
      (node (ref "U404") (pin "4") (pinfunction "IP-_4") (pintype "passive"))
    )
    (net (code "28") (name "Net-(J401-Pad2)") (class "Default")
      (node (ref "J401") (pin "2") (pinfunction "2_2") (pintype "passive"))
      (node (ref "L401") (pin "3") (pinfunction "3_3") (pintype "passive"))
    )
    (net (code "29") (name "Net-(L401-Pad2)") (class "Default")
      (node (ref "L401") (pin "2") (pinfunction "2_2") (pintype "passive"))
      (node (ref "U404") (pin "1") (pinfunction "IP+_1") (pintype "passive"))
      (node (ref "U404") (pin "2") (pinfunction "IP+_2") (pintype "passive"))
    )
    (net (code "30") (name "Net-(L403-Pad1)") (class "Default")
      (node (ref "L403") (pin "1") (pinfunction "1_1") (pintype "passive"))
      (node (ref "L404") (pin "2") (pinfunction "2_2") (pintype "passive"))
    )
    (net (code "31") (name "Net-(R401-Pad1)") (class "Default")
      (node (ref "R401") (pin "1") (pinfunction "1_1") (pintype "passive"))
      (node (ref "R402") (pin "2") (pinfunction "2_2") (pintype "passive"))
    )
    (net (code "32") (name "Net-(R402-Pad1)") (class "Default")
      (node (ref "R402") (pin "1") (pinfunction "1_1") (pintype "passive"))
      (node (ref "R403") (pin "2") (pinfunction "2_2") (pintype "passive"))
    )
    (net (code "33") (name "Net-(R404-Pad1)") (class "Default")
      (node (ref "R404") (pin "1") (pinfunction "1_1") (pintype "passive"))
      (node (ref "R407") (pin "2") (pinfunction "2_2") (pintype "passive"))
    )
    (net (code "34") (name "Net-(R405-Pad1)") (class "Default")
      (node (ref "R405") (pin "1") (pinfunction "1_1") (pintype "passive"))
      (node (ref "R408") (pin "2") (pinfunction "2_2") (pintype "passive"))
    )
    (net (code "35") (name "Net-(U401-VREF)") (class "Default")
      (node (ref "C425") (pin "1") (pinfunction "1_1") (pintype "passive"))
      (node (ref "R410") (pin "2") (pinfunction "2_2") (pintype "passive"))
      (node (ref "U401") (pin "6") (pinfunction "VREF_6") (pintype "passive"))
    )
    (net (code "36") (name "Net-(U402-VINP)") (class "Default")
      (node (ref "C416") (pin "1") (pinfunction "1_1") (pintype "passive"))
      (node (ref "R403") (pin "1") (pinfunction "1_1") (pintype "passive"))
      (node (ref "R406") (pin "2") (pinfunction "2_2") (pintype "passive"))
      (node (ref "U402") (pin "2") (pinfunction "VINP_2") (pintype "passive"))
    )
    (net (code "37") (name "Net-(U402-VOUTN)") (class "Default")
      (node (ref "R414") (pin "2") (pinfunction "2_2") (pintype "passive"))
      (node (ref "U402") (pin "6") (pinfunction "VOUTN_6") (pintype "passive"))
    )
    (net (code "38") (name "Net-(U402-VOUTP)") (class "Default")
      (node (ref "R415") (pin "2") (pinfunction "2_2") (pintype "passive"))
      (node (ref "U402") (pin "7") (pinfunction "VOUTP_7") (pintype "passive"))
    )
    (net (code "39") (name "Net-(U403-VREF)") (class "Default")
      (node (ref "C429") (pin "1") (pinfunction "1_1") (pintype "passive"))
      (node (ref "R412") (pin "2") (pinfunction "2_2") (pintype "passive"))
      (node (ref "U403") (pin "6") (pinfunction "VREF_6") (pintype "passive"))
    )
    (net (code "40") (name "Net-(U404-FILTER)") (class "Default")
      (node (ref "C438") (pin "1") (pinfunction "1_1") (pintype "passive"))
      (node (ref "U404") (pin "6") (pinfunction "FILTER_6") (pintype "passive"))
    )
    (net (code "41") (name "Net-(U404-VIOUT)") (class "Default")
      (node (ref "C436") (pin "1") (pinfunction "1_1") (pintype "passive"))
      (node (ref "R417") (pin "2") (pinfunction "2_2") (pintype "passive"))
      (node (ref "U404") (pin "7") (pinfunction "VIOUT_7") (pintype "passive"))
    )
    (net (code "42") (name "Net-(U405-DCDC_IN)") (class "Default")
      (node (ref "C439") (pin "1") (pinfunction "1_1") (pintype "passive"))
      (node (ref "U405") (pin "13") (pinfunction "LDO_OUT_13") (pintype "passive"))
      (node (ref "U405") (pin "16") (pinfunction "DCDC_IN_16") (pintype "power_in"))
    )
    (net (code "43") (name "Net-(U405-DCDC_OUT)") (class "Default")
      (node (ref "C420") (pin "2") (pinfunction "2_2") (pintype "passive"))
      (node (ref "C421") (pin "2") (pinfunction "2_2") (pintype "passive"))
      (node (ref "C422") (pin "2") (pinfunction "2_2") (pintype "passive"))
      (node (ref "U405") (pin "1") (pinfunction "DCDC_OUT_1") (pintype "passive"))
      (node (ref "U405") (pin "3") (pinfunction "HLDO_IN_3") (pintype "power_in"))
    )
    (net (code "44") (name "Net-(U405-DIAG)") (class "Default")
      (node (ref "C441") (pin "1") (pinfunction "1_1") (pintype "passive"))
      (node (ref "C442") (pin "1") (pinfunction "1_1") (pintype "passive"))
      (node (ref "FB401") (pin "2") (pinfunction "2_2") (pintype "passive"))
      (node (ref "R416") (pin "2") (pinfunction "2_2") (pintype "passive"))
      (node (ref "U405") (pin "14") (pinfunction "DIAG_14") (pintype "output"))
    )
    (net (code "45") (name "Net-(U405-HLDO_OUT)") (class "Default")
      (node (ref "C418") (pin "2") (pinfunction "2_2") (pintype "passive"))
      (node (ref "C419") (pin "2") (pinfunction "2_2") (pintype "passive"))
      (node (ref "U405") (pin "5") (pinfunction "HLDO_OUT_5") (pintype "output"))
    )
    (net (code "46") (name "Net-(U405-INP)") (class "Default")
      (node (ref "C417") (pin "2") (pinfunction "2_2") (pintype "passive"))
      (node (ref "R408") (pin "1") (pinfunction "1_1") (pintype "passive"))
      (node (ref "R409") (pin "2") (pinfunction "2_2") (pintype "passive"))
      (node (ref "U405") (pin "6") (pinfunction "INP_6") (pintype "passive"))
    )
    (net (code "47") (name "Net-(U405-OUTN)") (class "Default")
      (node (ref "R419") (pin "2") (pinfunction "2_2") (pintype "passive"))
      (node (ref "U405") (pin "10") (pinfunction "OUTN_10") (pintype "output"))
    )
    (net (code "48") (name "Net-(U405-OUTP)") (class "Default")
      (node (ref "R420") (pin "2") (pinfunction "2_2") (pintype "passive"))
      (node (ref "U405") (pin "11") (pinfunction "OUTP_11") (pintype "output"))
    )
    (net (code "49") (name "Net-(U405-VDD)") (class "Default")
      (node (ref "R416") (pin "1") (pinfunction "1_1") (pintype "passive"))
      (node (ref "U405") (pin "12") (pinfunction "VDD_12") (pintype "power_in"))
    )
    (net (code "50") (name "unconnected-(U401-VOUT-Pad7)") (class "Default")
      (node (ref "U401") (pin "7") (pinfunction "VOUT_7") (pintype "passive"))
    )
    (net (code "51") (name "unconnected-(U403-VOUT-Pad7)") (class "Default")
      (node (ref "U403") (pin "7") (pinfunction "VOUT_7") (pintype "passive"))
    )
    (net (code "52") (name "unconnected-(U405-NC-Pad4)") (class "Default")
      (node (ref "U405") (pin "4") (pinfunction "NC_4") (pintype "passive"))
    )
  )
)
